# Jack_In.net
KiCad netlist of a schematic drawn in Altium Designer
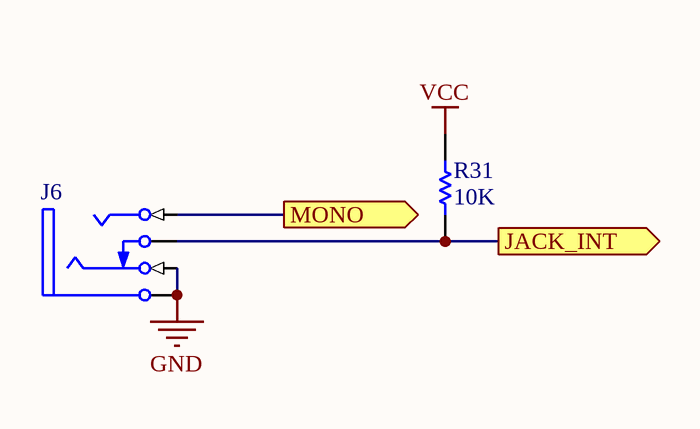
[diagram p0: Jack_In.SchDoc]

(export (version "E")
  (design (tool "Eeschema 10.0.6"))
  (components
    (comp (ref "J6")
      (value "Phonejack3 RN")
      (footprint "MHDR1X4")
      (description "Jack Socket, 1/4\" [6.5mm], Thru-Hole, Vertical, 3-Conductor with Tip open & Ring closed")
      (fields (field (name "PUBLISHER") "Altium Limited"))
      (libsource (lib "Miscellaneous Connectors") (part "Phonejack3 RN"))
    )
    (comp (ref "R31")
      (value "10K")
      (footprint "AXIAL-0.3")
      (description "Resistor")
      (fields (field (name "Comment") "Res1") (field (name "PUBLISHER") "Altium Limited"))
      (libsource (lib "Miscellaneous Devices") (part "Res1"))
    )
  )
  (nets
    (net (code "1") (name "/JACK_INT") (class "Default")
      (node (ref "J6") (pin "4") (pinfunction "RN_4") (pintype "passive"))
      (node (ref "R31") (pin "1") (pinfunction "1_1") (pintype "passive"))
    )
    (net (code "2") (name "/MONO") (class "Default")
      (node (ref "J6") (pin "1") (pinfunction "T_1") (pintype "input"))
    )
    (net (code "3") (name "GND") (class "Default")
      (node (ref "J6") (pin "3") (pinfunction "R_3") (pintype "input"))
      (node (ref "J6") (pin "5") (pinfunction "S_5") (pintype "power_in"))
    )
    (net (code "4") (name "VCC") (class "Default")
      (node (ref "R31") (pin "2") (pinfunction "2_2") (pintype "passive"))
    )
  )
)
